# CAN_SW.net
KiCad netlist of a schematic drawn in Altium Designer
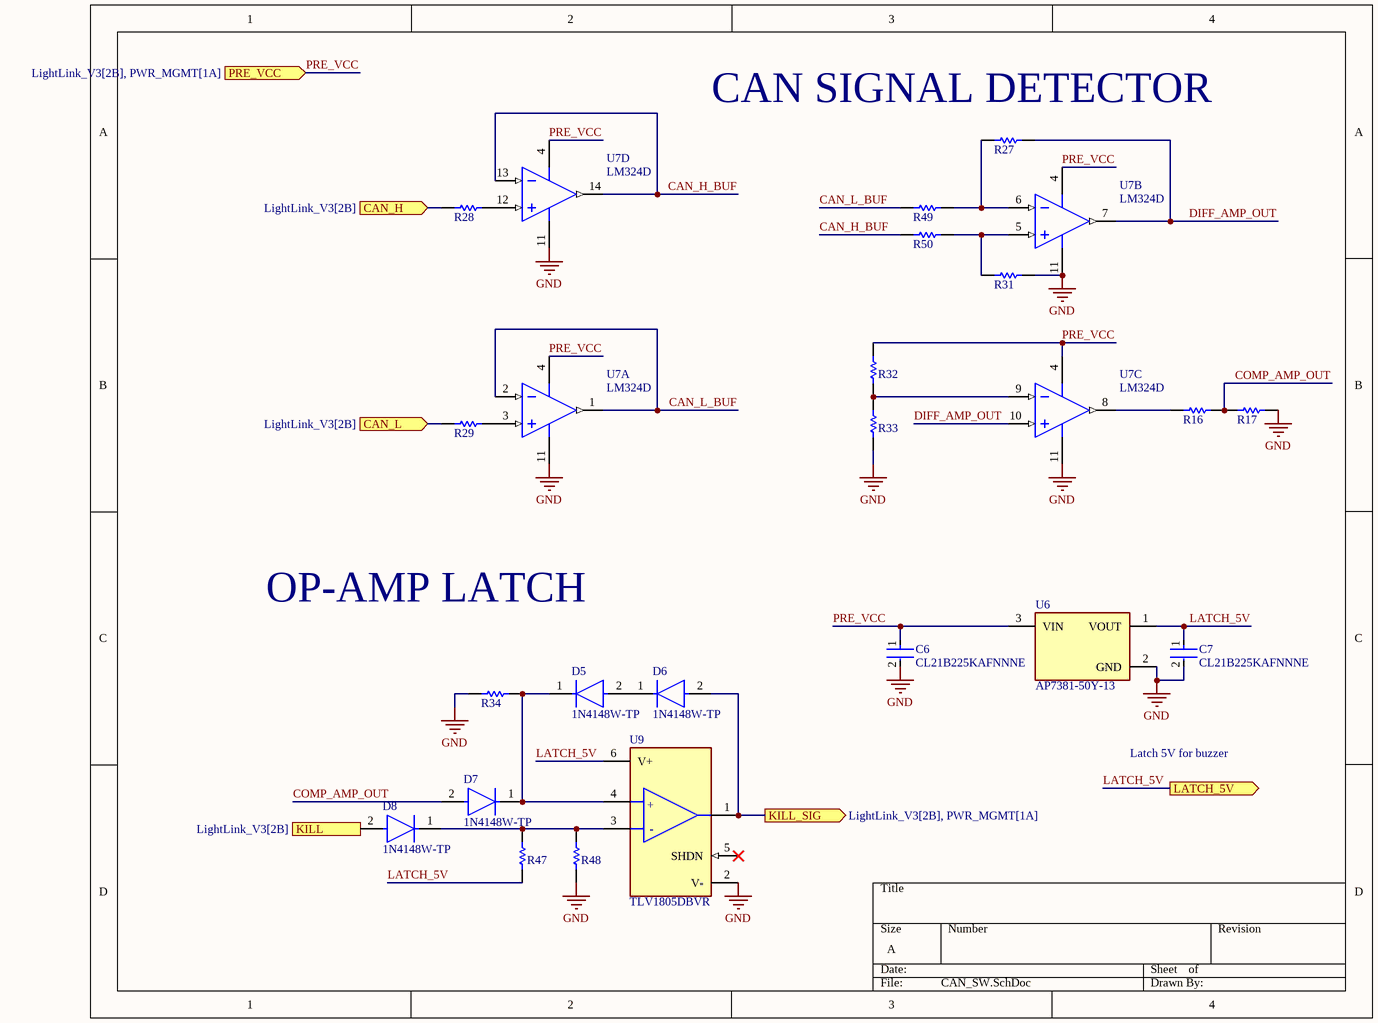
[diagram p0: CAN_SW.SchDoc]

(export (version "E")
  (design (tool "Eeschema 10.0.6"))
  (components
    (comp (ref "C6")
      (value "CL21B225KAFNNNE")
      (footprint "FP-0805-L_2_01_0_2-W_1_25-IPC_B")
      (fields (field (name "TOLERANCE") "10%") (field (name "VOLTAGE") "25V"))
      (libsource (lib "Altium Content Vault") (part "02cd4be3c70576c341d710602a673aa"))
    )
    (comp (ref "C7")
      (value "CL21B225KAFNNNE")
      (footprint "FP-0805-L_2_01_0_2-W_1_25-IPC_B")
      (fields (field (name "TOLERANCE") "10%") (field (name "VOLTAGE") "25V"))
      (libsource (lib "Altium Content Vault") (part "02cd4be3c70576c341d710602a673aa"))
    )
    (comp (ref "D5")
      (value "1N4148W-TP")
      (footprint "FP-SOD-123-IPC_A")
      (description "DIODE GEN PURP 100V 150MA SOD123")
      (libsource (lib "Altium Content Vault") (part "d7152d700b627762746794eb795d46e"))
    )
    (comp (ref "D6")
      (value "1N4148W-TP")
      (footprint "FP-SOD-123-IPC_A")
      (description "DIODE GEN PURP 100V 150MA SOD123")
      (libsource (lib "Altium Content Vault") (part "d7152d700b627762746794eb795d46e"))
    )
    (comp (ref "D7")
      (value "1N4148W-TP")
      (footprint "FP-SOD-123-IPC_A")
      (description "DIODE GEN PURP 100V 150MA SOD123")
      (libsource (lib "Altium Content Vault") (part "d7152d700b627762746794eb795d46e"))
    )
    (comp (ref "D8")
      (value "1N4148W-TP")
      (footprint "FP-SOD-123-IPC_A")
      (description "DIODE GEN PURP 100V 150MA SOD123")
      (libsource (lib "Altium Content Vault") (part "d7152d700b627762746794eb795d46e"))
    )
    (comp (ref "R16")
      (value "ERJ3EKF1002V")
      (footprint "RESC1609X55X30LL15T15")
      (description "Chip Resistor, 10 KOhm, +/- 1%, 0.1 W, -55 to 155 degC, 0603 (1608 Metric), RoHS, Tape and Reel")
      (fields (field (name "TOLERANCE") "1%") (field (name "MANUFACTURER") "Panasonic"))
      (libsource (lib "Altium Content Vault") (part "RES-2"))
    )
    (comp (ref "R17")
      (value "ERJ3EKF1002V")
      (footprint "RESC1609X55X30LL15T15")
      (description "Chip Resistor, 10 KOhm, +/- 1%, 0.1 W, -55 to 155 degC, 0603 (1608 Metric), RoHS, Tape and Reel")
      (fields (field (name "TOLERANCE") "1%") (field (name "MANUFACTURER") "Panasonic"))
      (libsource (lib "Altium Content Vault") (part "RES-2"))
    )
    (comp (ref "R27")
      (value "ERJ3EKF1002V")
      (footprint "RESC1609X55X30LL15T15")
      (description "Chip Resistor, 10 KOhm, +/- 1%, 0.1 W, -55 to 155 degC, 0603 (1608 Metric), RoHS, Tape and Reel")
      (fields (field (name "TOLERANCE") "1%") (field (name "MANUFACTURER") "Panasonic"))
      (libsource (lib "Altium Content Vault") (part "RES-2"))
    )
    (comp (ref "R28")
      (value "ERJ3EKF1002V")
      (footprint "RESC1609X55X30LL15T15")
      (description "Chip Resistor, 10 KOhm, +/- 1%, 0.1 W, -55 to 155 degC, 0603 (1608 Metric), RoHS, Tape and Reel")
      (fields (field (name "TOLERANCE") "1%") (field (name "MANUFACTURER") "Panasonic"))
      (libsource (lib "Altium Content Vault") (part "RES-2"))
    )
    (comp (ref "R29")
      (value "ERJ3EKF1002V")
      (footprint "RESC1609X55X30LL15T15")
      (description "Chip Resistor, 10 KOhm, +/- 1%, 0.1 W, -55 to 155 degC, 0603 (1608 Metric), RoHS, Tape and Reel")
      (fields (field (name "TOLERANCE") "1%") (field (name "MANUFACTURER") "Panasonic"))
      (libsource (lib "Altium Content Vault") (part "RES-2"))
    )
    (comp (ref "R31")
      (value "ERJ3EKF1002V")
      (footprint "RESC1609X55X30LL15T15")
      (description "Chip Resistor, 10 KOhm, +/- 1%, 0.1 W, -55 to 155 degC, 0603 (1608 Metric), RoHS, Tape and Reel")
      (fields (field (name "TOLERANCE") "1%") (field (name "MANUFACTURER") "Panasonic"))
      (libsource (lib "Altium Content Vault") (part "RES-2"))
    )
    (comp (ref "R32")
      (value "ERJ3EKF1002V")
      (footprint "RESC1609X55X30LL15T15")
      (description "Chip Resistor, 10 KOhm, +/- 1%, 0.1 W, -55 to 155 degC, 0603 (1608 Metric), RoHS, Tape and Reel")
      (fields (field (name "TOLERANCE") "1%") (field (name "MANUFACTURER") "Panasonic"))
      (libsource (lib "Altium Content Vault") (part "RES-2"))
    )
    (comp (ref "R33")
      (value "ERJ-3EKF1001V")
      (footprint "RESC1608X55X30LL15T15")
      (fields (field (name "MANUFACTURER") "Panasonic"))
      (libsource (lib "Altium Content Vault") (part "RES"))
    )
    (comp (ref "R34")
      (value "ERJ3EKF1002V")
      (footprint "RESC1609X55X30LL15T15")
      (description "Chip Resistor, 10 KOhm, +/- 1%, 0.1 W, -55 to 155 degC, 0603 (1608 Metric), RoHS, Tape and Reel")
      (fields (field (name "TOLERANCE") "1%") (field (name "MANUFACTURER") "Panasonic"))
      (libsource (lib "Altium Content Vault") (part "RES-2"))
    )
    (comp (ref "R47")
      (value "ERJ3EKF1002V")
      (footprint "RESC1609X55X30LL15T15")
      (description "Chip Resistor, 10 KOhm, +/- 1%, 0.1 W, -55 to 155 degC, 0603 (1608 Metric), RoHS, Tape and Reel")
      (fields (field (name "TOLERANCE") "1%") (field (name "MANUFACTURER") "Panasonic"))
      (libsource (lib "Altium Content Vault") (part "RES-2"))
    )
    (comp (ref "R48")
      (value "ERJ3EKF1002V")
      (footprint "RESC1609X55X30LL15T15")
      (description "Chip Resistor, 10 KOhm, +/- 1%, 0.1 W, -55 to 155 degC, 0603 (1608 Metric), RoHS, Tape and Reel")
      (fields (field (name "TOLERANCE") "1%") (field (name "MANUFACTURER") "Panasonic"))
      (libsource (lib "Altium Content Vault") (part "RES-2"))
    )
    (comp (ref "R49")
      (value "ERJ3EKF1002V")
      (footprint "RESC1609X55X30LL15T15")
      (description "Chip Resistor, 10 KOhm, +/- 1%, 0.1 W, -55 to 155 degC, 0603 (1608 Metric), RoHS, Tape and Reel")
      (fields (field (name "TOLERANCE") "1%") (field (name "MANUFACTURER") "Panasonic"))
      (libsource (lib "Altium Content Vault") (part "RES-2"))
    )
    (comp (ref "R50")
      (value "ERJ3EKF1002V")
      (footprint "RESC1609X55X30LL15T15")
      (description "Chip Resistor, 10 KOhm, +/- 1%, 0.1 W, -55 to 155 degC, 0603 (1608 Metric), RoHS, Tape and Reel")
      (fields (field (name "TOLERANCE") "1%") (field (name "MANUFACTURER") "Panasonic"))
      (libsource (lib "Altium Content Vault") (part "RES-2"))
    )
    (comp (ref "U6")
      (value "AP7381-50Y-13")
      (footprint "FP-SOT89-MFG")
      (description "IC REG LINEAR 5V 150MA SOT89")
      (fields
        (field (name "MANUFACTURER") "Diodes Inc.")
        (field (name "OCTOPART") "https://octopart.com/ap7381-50y-13-diodes+inc.-87775116")
      )
      (libsource (lib "Altium Content Vault") (part "4c3da590f2d7b1882ad42f13e6d336b"))
    )
    (comp (ref "U7")
      (value "LM324D")
      (footprint "D0014A_L")
      (fields (field (name "MANUFACTURER") "Texas Instruments"))
      (libsource (lib "Altium Content Vault") (part "TI-LMX24_2902X-X14"))
    )
    (comp (ref "U9")
      (value "TLV1805DBVR")
      (footprint "FP-DBV0006A-IPC_C")
      (description "40V, RAIL-TO-RAIL INPUT, PUSH-PU")
      (libsource (lib "Altium Content Vault") (part "c7aa3bc3dbf0dc8b0b0354779bd1228"))
    )
  )
  (nets
    (net (code "1") (name "/CAN_H") (class "Default")
      (node (ref "R28") (pin "1") (pinfunction "1_1") (pintype "passive"))
    )
    (net (code "2") (name "/CAN_H_BUF") (class "Default")
      (node (ref "R50") (pin "1") (pinfunction "1_1") (pintype "passive"))
      (node (ref "U7") (pin "13") (pinfunction "4IN-_13") (pintype "input"))
      (node (ref "U7") (pin "14") (pinfunction "4OUT_14") (pintype "output"))
    )
    (net (code "3") (name "/CAN_L") (class "Default")
      (node (ref "R29") (pin "1") (pinfunction "1_1") (pintype "passive"))
    )
    (net (code "4") (name "/CAN_L_BUF") (class "Default")
      (node (ref "R49") (pin "1") (pinfunction "1_1") (pintype "passive"))
      (node (ref "U7") (pin "1") (pinfunction "1OUT_1") (pintype "output"))
      (node (ref "U7") (pin "2") (pinfunction "1IN-_2") (pintype "input"))
    )
    (net (code "5") (name "/COMP_AMP_OUT") (class "Default")
      (node (ref "D7") (pin "2") (pinfunction "A_2") (pintype "passive"))
      (node (ref "R16") (pin "1") (pinfunction "1_1") (pintype "passive"))
      (node (ref "R17") (pin "2") (pinfunction "2_2") (pintype "passive"))
    )
    (net (code "6") (name "/DIFF_AMP_OUT") (class "Default")
      (node (ref "R27") (pin "2") (pinfunction "2_2") (pintype "passive"))
      (node (ref "U7") (pin "10") (pinfunction "3IN+_10") (pintype "input"))
      (node (ref "U7") (pin "7") (pinfunction "2OUT_7") (pintype "output"))
    )
    (net (code "7") (name "/KILL") (class "Default")
      (node (ref "D8") (pin "2") (pinfunction "A_2") (pintype "passive"))
    )
    (net (code "8") (name "/KILL_SIG") (class "Default")
      (node (ref "D6") (pin "2") (pinfunction "A_2") (pintype "passive"))
      (node (ref "U9") (pin "1") (pinfunction "OUT_1") (pintype "passive"))
    )
    (net (code "9") (name "/LATCH_5V") (class "Default")
      (node (ref "C7") (pin "1") (pinfunction "1_1") (pintype "passive"))
      (node (ref "R47") (pin "1") (pinfunction "1_1") (pintype "passive"))
      (node (ref "U6") (pin "1") (pinfunction "VOUT_1") (pintype "power_in"))
      (node (ref "U9") (pin "6") (pinfunction "V+_6") (pintype "power_in"))
    )
    (net (code "10") (name "/PRE_VCC") (class "Default")
      (node (ref "C6") (pin "1") (pinfunction "1_1") (pintype "passive"))
      (node (ref "R32") (pin "2") (pinfunction "2_2") (pintype "passive"))
      (node (ref "U6") (pin "3") (pinfunction "VIN_3") (pintype "power_in"))
      (node (ref "U7") (pin "4") (pinfunction "VCC_4") (pintype "power_in"))
    )
    (net (code "11") (name "GND") (class "Default")
      (node (ref "C6") (pin "2") (pinfunction "2_2") (pintype "passive"))
      (node (ref "C7") (pin "2") (pinfunction "2_2") (pintype "passive"))
      (node (ref "R17") (pin "1") (pinfunction "1_1") (pintype "passive"))
      (node (ref "R31") (pin "2") (pinfunction "2_2") (pintype "passive"))
      (node (ref "R33") (pin "1") (pinfunction "1_1") (pintype "passive"))
      (node (ref "R34") (pin "2") (pinfunction "2_2") (pintype "passive"))
      (node (ref "R48") (pin "1") (pinfunction "1_1") (pintype "passive"))
      (node (ref "U6") (pin "2") (pinfunction "GND_2") (pintype "power_in"))
      (node (ref "U7") (pin "11") (pinfunction "GND_11") (pintype "power_in"))
      (node (ref "U9") (pin "2") (pinfunction "V-_2") (pintype "power_in"))
    )
    (net (code "12") (name "Net-(D5-A)") (class "Default")
      (node (ref "D5") (pin "2") (pinfunction "A_2") (pintype "passive"))
      (node (ref "D6") (pin "1") (pinfunction "C_1") (pintype "passive"))
    )
    (net (code "13") (name "Net-(D5-C)") (class "Default")
      (node (ref "D5") (pin "1") (pinfunction "C_1") (pintype "passive"))
      (node (ref "D7") (pin "1") (pinfunction "C_1") (pintype "passive"))
      (node (ref "R34") (pin "1") (pinfunction "1_1") (pintype "passive"))
      (node (ref "U9") (pin "4") (pinfunction "+IN_4") (pintype "tri_state"))
    )
    (net (code "14") (name "Net-(D8-C)") (class "Default")
      (node (ref "D8") (pin "1") (pinfunction "C_1") (pintype "passive"))
      (node (ref "R47") (pin "2") (pinfunction "2_2") (pintype "passive"))
      (node (ref "R48") (pin "2") (pinfunction "2_2") (pintype "passive"))
      (node (ref "U9") (pin "3") (pinfunction "-IN_3") (pintype "tri_state"))
    )
    (net (code "15") (name "Net-(U7A-1IN+)") (class "Default")
      (node (ref "R29") (pin "2") (pinfunction "2_2") (pintype "passive"))
      (node (ref "U7") (pin "3") (pinfunction "1IN+_3") (pintype "input"))
    )
    (net (code "16") (name "Net-(U7B-2IN+)") (class "Default")
      (node (ref "R31") (pin "1") (pinfunction "1_1") (pintype "passive"))
      (node (ref "R50") (pin "2") (pinfunction "2_2") (pintype "passive"))
      (node (ref "U7") (pin "5") (pinfunction "2IN+_5") (pintype "input"))
    )
    (net (code "17") (name "Net-(U7B-2IN-)") (class "Default")
      (node (ref "R27") (pin "1") (pinfunction "1_1") (pintype "passive"))
      (node (ref "R49") (pin "2") (pinfunction "2_2") (pintype "passive"))
      (node (ref "U7") (pin "6") (pinfunction "2IN-_6") (pintype "input"))
    )
    (net (code "18") (name "Net-(U7C-3IN-)") (class "Default")
      (node (ref "R32") (pin "1") (pinfunction "1_1") (pintype "passive"))
      (node (ref "R33") (pin "2") (pinfunction "2_2") (pintype "passive"))
      (node (ref "U7") (pin "9") (pinfunction "3IN-_9") (pintype "input"))
    )
    (net (code "19") (name "Net-(U7C-3OUT)") (class "Default")
      (node (ref "R16") (pin "2") (pinfunction "2_2") (pintype "passive"))
      (node (ref "U7") (pin "8") (pinfunction "3OUT_8") (pintype "output"))
    )
    (net (code "20") (name "Net-(U7D-4IN+)") (class "Default")
      (node (ref "R28") (pin "2") (pinfunction "2_2") (pintype "passive"))
      (node (ref "U7") (pin "12") (pinfunction "4IN+_12") (pintype "input"))
    )
    (net (code "21") (name "unconnected-(U9-SHDN-Pad5)") (class "Default")
      (node (ref "U9") (pin "5") (pinfunction "SHDN_5") (pintype "input+no_connect"))
    )
  )
)
